# LED_Breakout_Board_V7.net
KiCad netlist of a schematic drawn in EAGLE
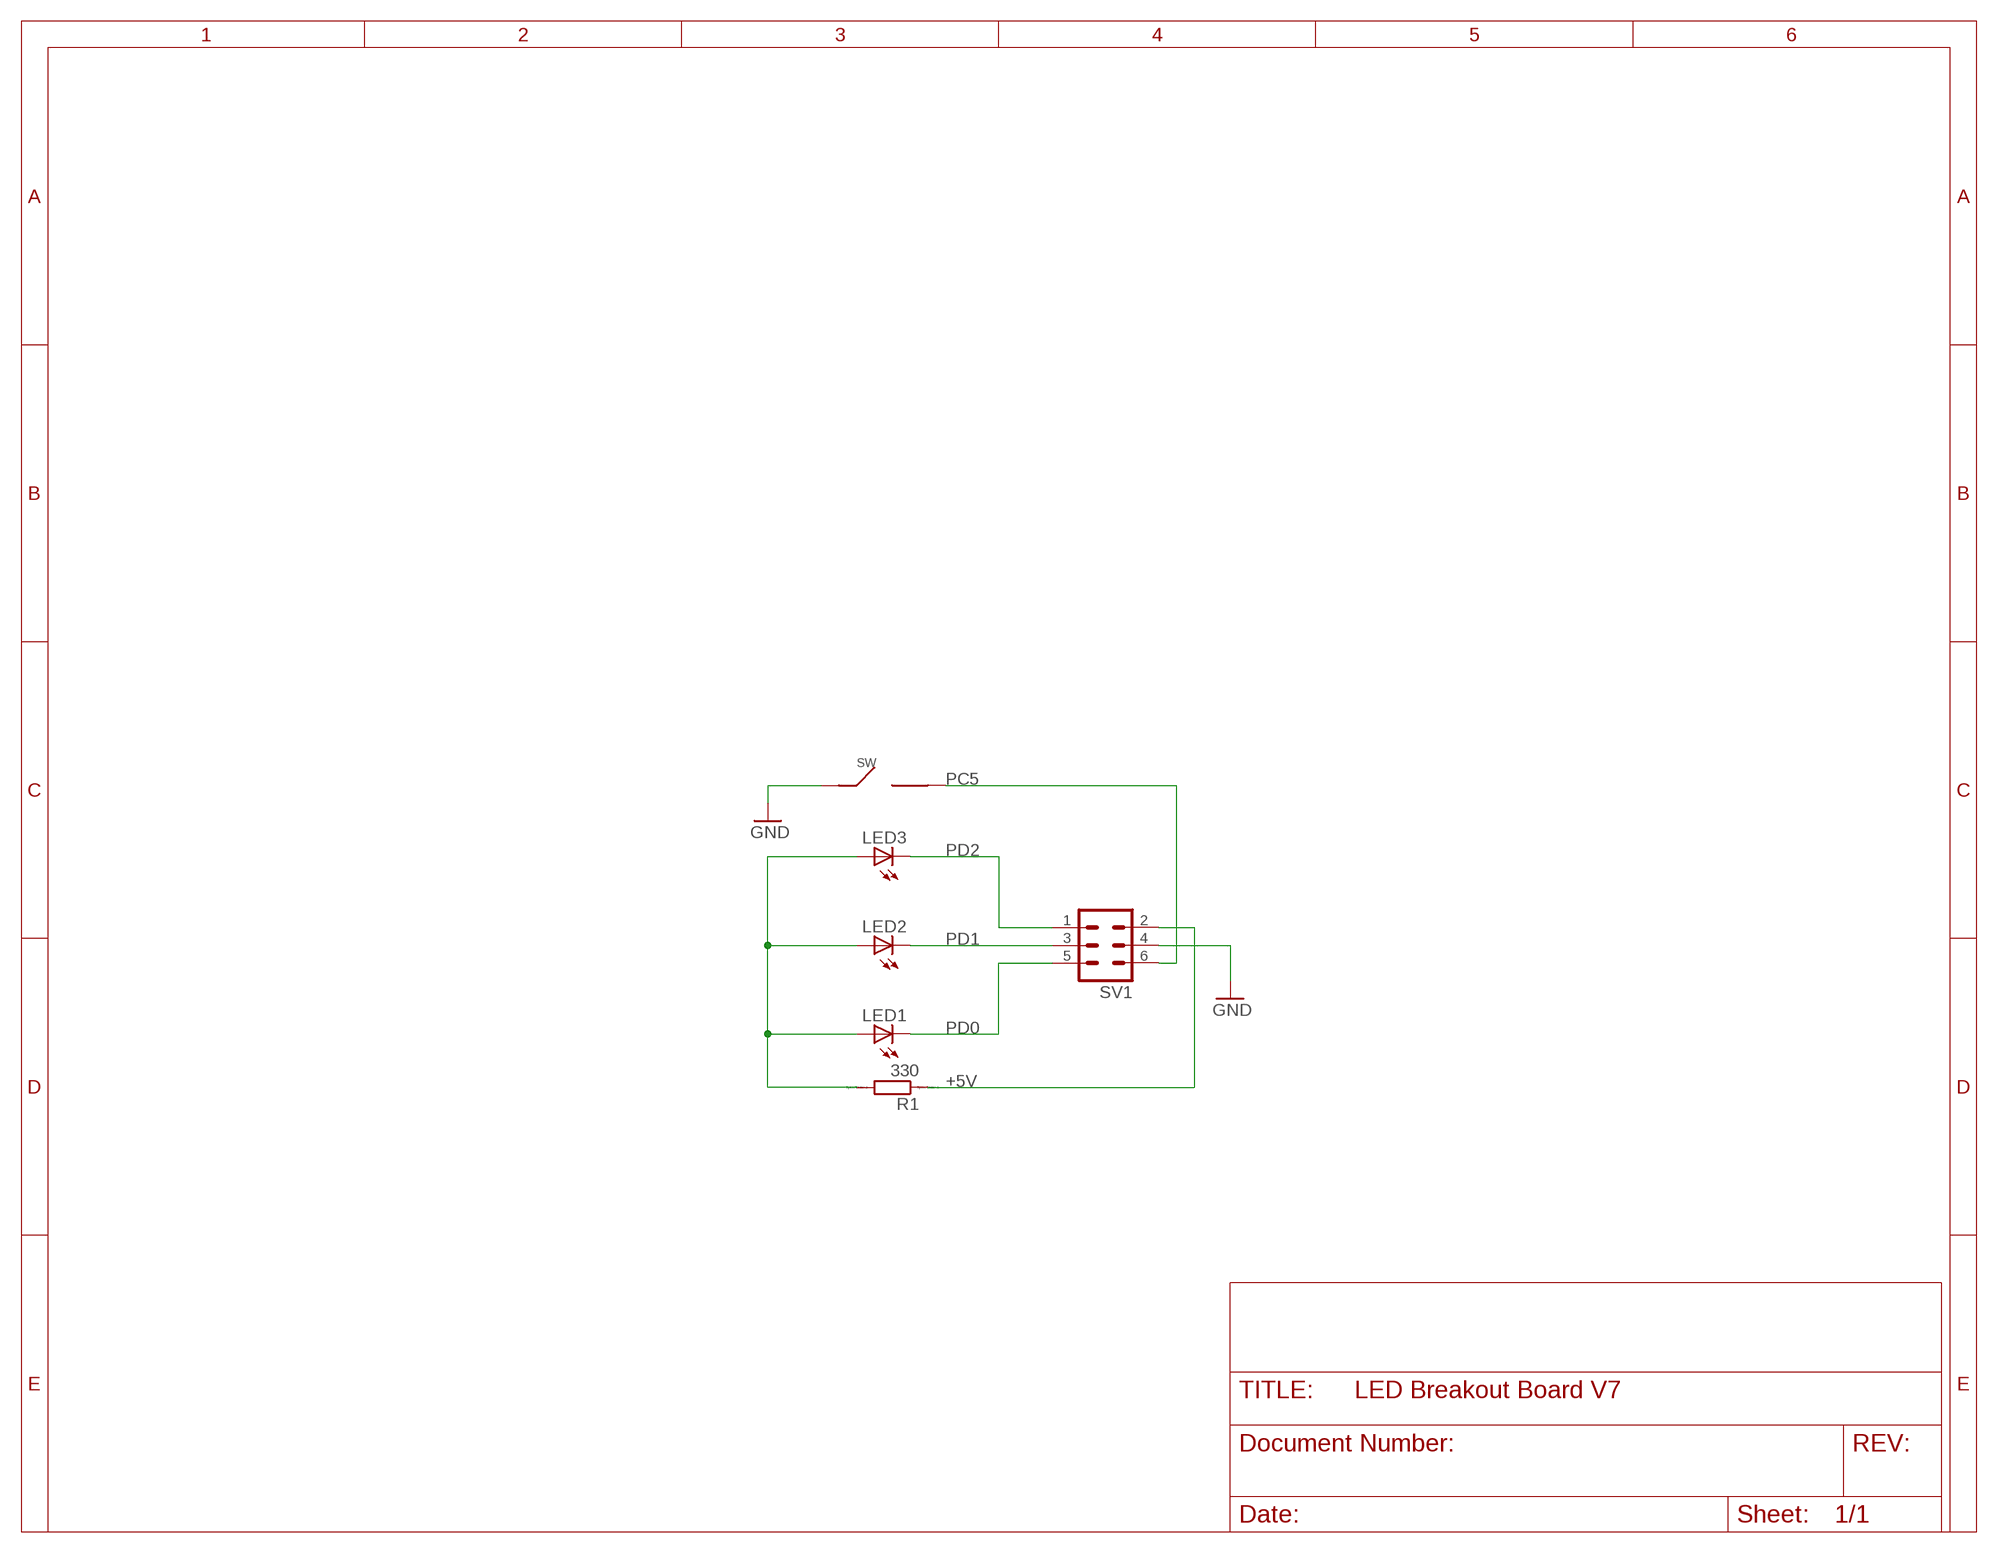
[diagram p0: schematic, sheet 1]

(export (version "E")
  (design (tool "Eeschema 10.0.6"))
  (components
    (comp (ref "LED1")
      (value "LED10MM")
      (footprint "eagle-import:LED10MM")
      (libsource (lib "eagle-import") (part "LED10MM"))
    )
    (comp (ref "LED2")
      (value "LED10MM")
      (footprint "eagle-import:LED10MM")
      (libsource (lib "eagle-import") (part "LED10MM"))
    )
    (comp (ref "LED3")
      (value "LED10MM")
      (footprint "eagle-import:LED10MM")
      (libsource (lib "eagle-import") (part "LED10MM"))
    )
    (comp (ref "R1")
      (value "330")
      (footprint "eagle-import:0204_7")
      (libsource (lib "eagle-import") (part "R0204/7"))
    )
    (comp (ref "SV1")
      (value "MA03-2")
      (footprint "eagle-import:MA03-2")
      (libsource (lib "eagle-import") (part "MA03-2"))
    )
    (comp (ref "SW")
      (value "PUSHBUTTON")
      (footprint "eagle-import:PUSHBUTTON")
      (libsource (lib "eagle-import") (part "PUSHBUTTON"))
    )
  )
  (nets
    (net (code "1") (name "/+5V") (class "Default")
      (node (ref "R1") (pin "1") (pinfunction "1_1") (pintype "passive"))
      (node (ref "SV1") (pin "2") (pinfunction "2_2") (pintype "passive"))
    )
    (net (code "2") (name "/PC5") (class "Default")
      (node (ref "SV1") (pin "6") (pinfunction "6_6") (pintype "passive"))
      (node (ref "SW") (pin "OUT") (pinfunction "OUT_OUT") (pintype "bidirectional"))
    )
    (net (code "3") (name "/PD0") (class "Default")
      (node (ref "LED1") (pin "K") (pinfunction "C_K") (pintype "passive"))
      (node (ref "SV1") (pin "5") (pinfunction "5_5") (pintype "passive"))
    )
    (net (code "4") (name "/PD1") (class "Default")
      (node (ref "LED2") (pin "K") (pinfunction "C_K") (pintype "passive"))
      (node (ref "SV1") (pin "3") (pinfunction "3_3") (pintype "passive"))
    )
    (net (code "5") (name "/PD2") (class "Default")
      (node (ref "LED3") (pin "K") (pinfunction "C_K") (pintype "passive"))
      (node (ref "SV1") (pin "1") (pinfunction "1_1") (pintype "passive"))
    )
    (net (code "6") (name "GND") (class "Default")
      (node (ref "SV1") (pin "4") (pinfunction "4_4") (pintype "passive"))
      (node (ref "SW") (pin "IN") (pinfunction "IN_IN") (pintype "bidirectional"))
    )
    (net (code "7") (name "Net-(LED1-PadA)") (class "Default")
      (node (ref "LED1") (pin "A") (pinfunction "A_A") (pintype "passive"))
      (node (ref "LED2") (pin "A") (pinfunction "A_A") (pintype "passive"))
      (node (ref "LED3") (pin "A") (pinfunction "A_A") (pintype "passive"))
      (node (ref "R1") (pin "2") (pinfunction "2_2") (pintype "passive"))
    )
  )
)
